# Altium_-_Maltron_S_Edition_-_Schematic.net
KiCad netlist of a schematic drawn in Altium Designer
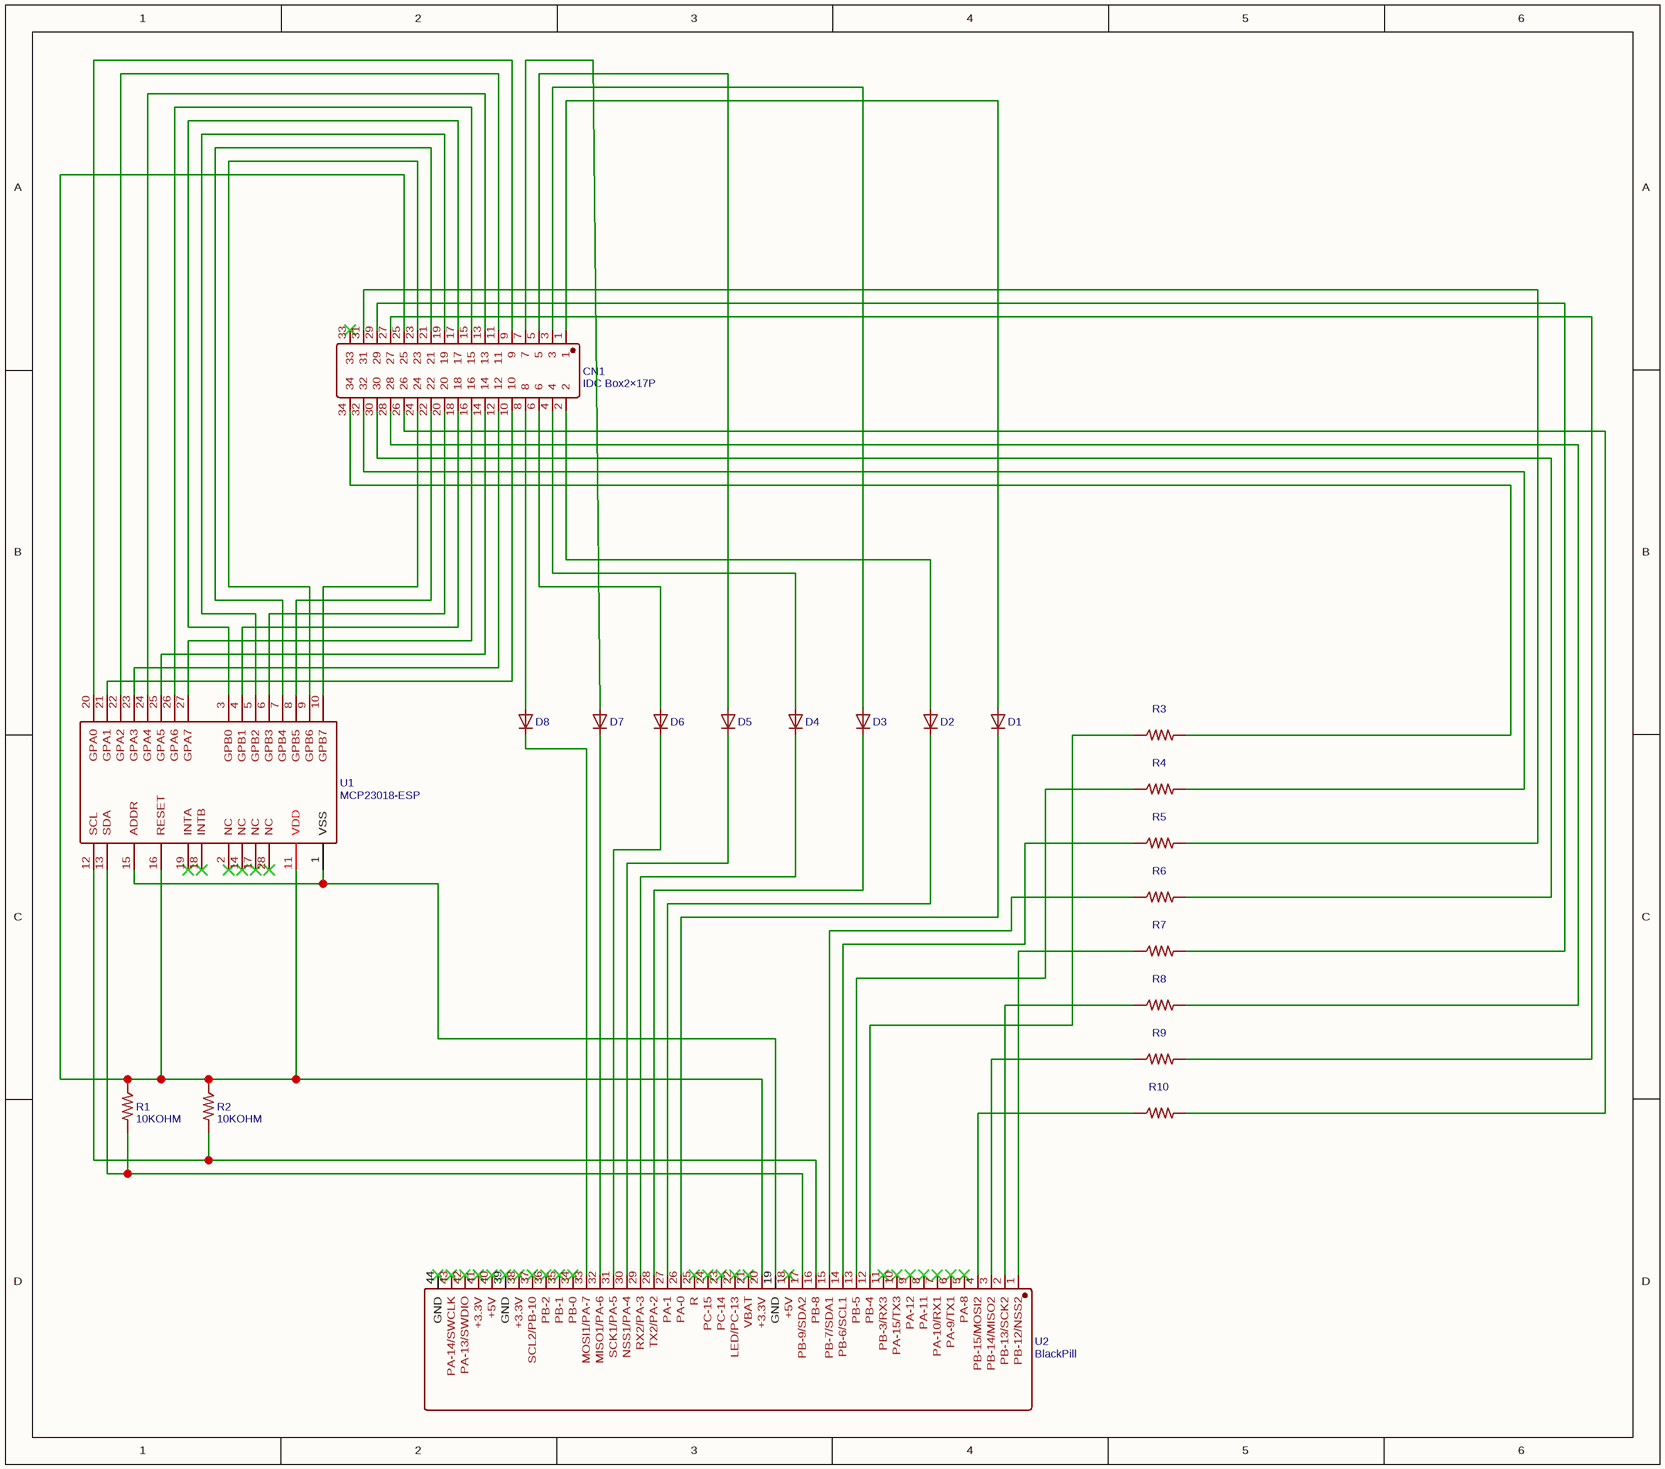
[diagram p0: Altium - Maltron_S_Edition - Schematic.schdoc]

(export (version "E")
  (design (tool "Eeschema 10.0.6"))
  (components
    (comp (ref "CN1")
      (value "IDC Box2×17P")
      (fields
        (field (name "BOM_MANUFACTURER PART") "IDC Box2×17P Right Angle")
        (field (name "BOM_SUPPLIER PART") "C20920")
      )
      (libsource (lib "altium-import") (part "root_3_IDC Box2×17P_"))
    )
    (comp (ref "D1")
      (value "DIODE")
      (fields (field (name "CONTRIBUTOR") "Adafruit"))
      (libsource (lib "altium-import") (part "root_3_DIODE_"))
    )
    (comp (ref "D2")
      (value "DIODE")
      (fields (field (name "CONTRIBUTOR") "Adafruit"))
      (libsource (lib "altium-import") (part "root_3_DIODE_"))
    )
    (comp (ref "D3")
      (value "DIODE")
      (fields (field (name "CONTRIBUTOR") "Adafruit"))
      (libsource (lib "altium-import") (part "root_3_DIODE_"))
    )
    (comp (ref "D4")
      (value "DIODE")
      (fields (field (name "CONTRIBUTOR") "Adafruit"))
      (libsource (lib "altium-import") (part "root_3_DIODE_"))
    )
    (comp (ref "D5")
      (value "DIODE")
      (fields (field (name "CONTRIBUTOR") "Adafruit"))
      (libsource (lib "altium-import") (part "root_3_DIODE_"))
    )
    (comp (ref "D6")
      (value "DIODE")
      (fields (field (name "CONTRIBUTOR") "Adafruit"))
      (libsource (lib "altium-import") (part "root_3_DIODE_"))
    )
    (comp (ref "D7")
      (value "DIODE")
      (fields (field (name "CONTRIBUTOR") "Adafruit"))
      (libsource (lib "altium-import") (part "root_3_DIODE_"))
    )
    (comp (ref "D8")
      (value "DIODE")
      (fields (field (name "CONTRIBUTOR") "Adafruit"))
      (libsource (lib "altium-import") (part "root_3_DIODE_"))
    )
    (comp (ref "R1")
      (value "10KOHM")
      (description "RES-09435")
      (fields (field (name "CONTRIBUTOR") "SparkFun"))
      (libsource (lib "altium-import") (part "root_3_10KOHM_"))
    )
    (comp (ref "R2")
      (value "10KOHM")
      (description "RES-09435")
      (fields (field (name "CONTRIBUTOR") "SparkFun"))
      (libsource (lib "altium-import") (part "root_3_10KOHM_"))
    )
    (comp (ref "R3")
      (value "10OHM-1_4W-5%(PTH)HORIZ-KIT")
      (description "RES-10698")
      (fields (field (name "CONTRIBUTOR") "SparkFun"))
      (libsource (lib "altium-import") (part "root_0_10OHM-1_4W-5%(PTH)HORIZ-KIT_"))
    )
    (comp (ref "R4")
      (value "10OHM-1_4W-5%(PTH)HORIZ-KIT")
      (description "RES-10698")
      (fields (field (name "CONTRIBUTOR") "SparkFun"))
      (libsource (lib "altium-import") (part "root_0_10OHM-1_4W-5%(PTH)HORIZ-KIT_"))
    )
    (comp (ref "R5")
      (value "10OHM-1_4W-5%(PTH)HORIZ-KIT")
      (description "RES-10698")
      (fields (field (name "CONTRIBUTOR") "SparkFun"))
      (libsource (lib "altium-import") (part "root_0_10OHM-1_4W-5%(PTH)HORIZ-KIT_"))
    )
    (comp (ref "R6")
      (value "10OHM-1_4W-5%(PTH)HORIZ-KIT")
      (description "RES-10698")
      (fields (field (name "CONTRIBUTOR") "SparkFun"))
      (libsource (lib "altium-import") (part "root_0_10OHM-1_4W-5%(PTH)HORIZ-KIT_"))
    )
    (comp (ref "R7")
      (value "10OHM-1_4W-5%(PTH)HORIZ-KIT")
      (description "RES-10698")
      (fields (field (name "CONTRIBUTOR") "SparkFun"))
      (libsource (lib "altium-import") (part "root_0_10OHM-1_4W-5%(PTH)HORIZ-KIT_"))
    )
    (comp (ref "R8")
      (value "10OHM-1_4W-5%(PTH)HORIZ-KIT")
      (description "RES-10698")
      (fields (field (name "CONTRIBUTOR") "SparkFun"))
      (libsource (lib "altium-import") (part "root_0_10OHM-1_4W-5%(PTH)HORIZ-KIT_"))
    )
    (comp (ref "R9")
      (value "10OHM-1_4W-5%(PTH)HORIZ-KIT")
      (description "RES-10698")
      (fields (field (name "CONTRIBUTOR") "SparkFun"))
      (libsource (lib "altium-import") (part "root_0_10OHM-1_4W-5%(PTH)HORIZ-KIT_"))
    )
    (comp (ref "R10")
      (value "10OHM-1_4W-5%(PTH)HORIZ-KIT")
      (description "RES-10698")
      (fields (field (name "CONTRIBUTOR") "SparkFun"))
      (libsource (lib "altium-import") (part "root_0_10OHM-1_4W-5%(PTH)HORIZ-KIT_"))
    )
    (comp (ref "U1") (value "MCP23018-ESP") (libsource (lib "altium-import") (part "root_1_MCP23018-ESP_")))
    (comp (ref "U2")
      (value "BlackPill")
      (fields (field (name "CONTRIBUTOR") "Michael Schramm"))
      (libsource (lib "altium-import") (part "root_3_BlackPill_"))
    )
  )
  (nets
    (net (code "1") (name "Net-(CN1-Pad1)") (class "Default")
      (node (ref "CN1") (pin "1") (pinfunction "1_1") (pintype "passive"))
      (node (ref "D1") (pin "A") (pinfunction "A_A") (pintype "passive"))
    )
    (net (code "2") (name "Net-(CN1-Pad2)") (class "Default")
      (node (ref "CN1") (pin "2") (pinfunction "2_2") (pintype "passive"))
      (node (ref "D2") (pin "A") (pinfunction "A_A") (pintype "passive"))
    )
    (net (code "3") (name "Net-(CN1-Pad3)") (class "Default")
      (node (ref "CN1") (pin "3") (pinfunction "3_3") (pintype "passive"))
      (node (ref "D3") (pin "A") (pinfunction "A_A") (pintype "passive"))
    )
    (net (code "4") (name "Net-(CN1-Pad4)") (class "Default")
      (node (ref "CN1") (pin "4") (pinfunction "4_4") (pintype "passive"))
      (node (ref "D4") (pin "A") (pinfunction "A_A") (pintype "passive"))
    )
    (net (code "5") (name "Net-(CN1-Pad5)") (class "Default")
      (node (ref "CN1") (pin "5") (pinfunction "5_5") (pintype "passive"))
      (node (ref "D5") (pin "A") (pinfunction "A_A") (pintype "passive"))
    )
    (net (code "6") (name "Net-(CN1-Pad6)") (class "Default")
      (node (ref "CN1") (pin "6") (pinfunction "6_6") (pintype "passive"))
      (node (ref "D6") (pin "A") (pinfunction "A_A") (pintype "passive"))
    )
    (net (code "7") (name "Net-(CN1-Pad7)") (class "Default")
      (node (ref "CN1") (pin "7") (pinfunction "7_7") (pintype "passive"))
      (node (ref "D7") (pin "A") (pinfunction "A_A") (pintype "passive"))
    )
    (net (code "8") (name "Net-(CN1-Pad8)") (class "Default")
      (node (ref "CN1") (pin "8") (pinfunction "8_8") (pintype "passive"))
      (node (ref "D8") (pin "A") (pinfunction "A_A") (pintype "passive"))
    )
    (net (code "9") (name "Net-(CN1-Pad26)") (class "Default")
      (node (ref "CN1") (pin "26") (pinfunction "26_26") (pintype "passive"))
      (node (ref "R10") (pin "2") (pinfunction "2_2") (pintype "passive"))
    )
    (net (code "10") (name "Net-(CN1-Pad27)") (class "Default")
      (node (ref "CN1") (pin "27") (pinfunction "27_27") (pintype "passive"))
      (node (ref "R9") (pin "2") (pinfunction "2_2") (pintype "passive"))
    )
    (net (code "11") (name "Net-(CN1-Pad28)") (class "Default")
      (node (ref "CN1") (pin "28") (pinfunction "28_28") (pintype "passive"))
      (node (ref "R8") (pin "2") (pinfunction "2_2") (pintype "passive"))
    )
    (net (code "12") (name "Net-(CN1-Pad29)") (class "Default")
      (node (ref "CN1") (pin "29") (pinfunction "29_29") (pintype "passive"))
      (node (ref "R7") (pin "2") (pinfunction "2_2") (pintype "passive"))
    )
    (net (code "13") (name "Net-(CN1-Pad30)") (class "Default")
      (node (ref "CN1") (pin "30") (pinfunction "30_30") (pintype "passive"))
      (node (ref "R6") (pin "2") (pinfunction "2_2") (pintype "passive"))
    )
    (net (code "14") (name "Net-(CN1-Pad31)") (class "Default")
      (node (ref "CN1") (pin "31") (pinfunction "31_31") (pintype "passive"))
      (node (ref "R5") (pin "2") (pinfunction "2_2") (pintype "passive"))
    )
    (net (code "15") (name "Net-(CN1-Pad32)") (class "Default")
      (node (ref "CN1") (pin "32") (pinfunction "32_32") (pintype "passive"))
      (node (ref "R4") (pin "2") (pinfunction "2_2") (pintype "passive"))
    )
    (net (code "16") (name "Net-(CN1-Pad34)") (class "Default")
      (node (ref "CN1") (pin "34") (pinfunction "34_34") (pintype "passive"))
      (node (ref "R3") (pin "2") (pinfunction "2_2") (pintype "passive"))
    )
    (net (code "17") (name "Net-(U1-ADDR)") (class "Default")
      (node (ref "U1") (pin "1") (pinfunction "VSS_1") (pintype "passive"))
      (node (ref "U1") (pin "15") (pinfunction "ADDR_15") (pintype "passive"))
      (node (ref "U2") (pin "19") (pinfunction "GND_19") (pintype "passive"))
    )
    (net (code "18") (name "Net-(U1-GPA0)") (class "Default")
      (node (ref "CN1") (pin "9") (pinfunction "9_9") (pintype "passive"))
      (node (ref "U1") (pin "20") (pinfunction "GPA0_20") (pintype "passive"))
    )
    (net (code "19") (name "Net-(U1-GPA1)") (class "Default")
      (node (ref "CN1") (pin "10") (pinfunction "10_10") (pintype "passive"))
      (node (ref "U1") (pin "21") (pinfunction "GPA1_21") (pintype "passive"))
    )
    (net (code "20") (name "Net-(U1-GPA2)") (class "Default")
      (node (ref "CN1") (pin "11") (pinfunction "11_11") (pintype "passive"))
      (node (ref "U1") (pin "22") (pinfunction "GPA2_22") (pintype "passive"))
    )
    (net (code "21") (name "Net-(U1-GPA3)") (class "Default")
      (node (ref "CN1") (pin "12") (pinfunction "12_12") (pintype "passive"))
      (node (ref "U1") (pin "23") (pinfunction "GPA3_23") (pintype "passive"))
    )
    (net (code "22") (name "Net-(U1-GPA4)") (class "Default")
      (node (ref "CN1") (pin "13") (pinfunction "13_13") (pintype "passive"))
      (node (ref "U1") (pin "24") (pinfunction "GPA4_24") (pintype "passive"))
    )
    (net (code "23") (name "Net-(U1-GPA5)") (class "Default")
      (node (ref "CN1") (pin "14") (pinfunction "14_14") (pintype "passive"))
      (node (ref "U1") (pin "25") (pinfunction "GPA5_25") (pintype "passive"))
    )
    (net (code "24") (name "Net-(U1-GPA6)") (class "Default")
      (node (ref "CN1") (pin "15") (pinfunction "15_15") (pintype "passive"))
      (node (ref "U1") (pin "26") (pinfunction "GPA6_26") (pintype "passive"))
    )
    (net (code "25") (name "Net-(U1-GPA7)") (class "Default")
      (node (ref "CN1") (pin "16") (pinfunction "16_16") (pintype "passive"))
      (node (ref "U1") (pin "27") (pinfunction "GPA7_27") (pintype "passive"))
    )
    (net (code "26") (name "Net-(U1-GPB0)") (class "Default")
      (node (ref "CN1") (pin "17") (pinfunction "17_17") (pintype "passive"))
      (node (ref "U1") (pin "3") (pinfunction "GPB0_3") (pintype "passive"))
    )
    (net (code "27") (name "Net-(U1-GPB1)") (class "Default")
      (node (ref "CN1") (pin "18") (pinfunction "18_18") (pintype "passive"))
      (node (ref "U1") (pin "4") (pinfunction "GPB1_4") (pintype "passive"))
    )
    (net (code "28") (name "Net-(U1-GPB2)") (class "Default")
      (node (ref "CN1") (pin "19") (pinfunction "19_19") (pintype "passive"))
      (node (ref "U1") (pin "5") (pinfunction "GPB2_5") (pintype "passive"))
    )
    (net (code "29") (name "Net-(U1-GPB3)") (class "Default")
      (node (ref "CN1") (pin "20") (pinfunction "20_20") (pintype "passive"))
      (node (ref "U1") (pin "6") (pinfunction "GPB3_6") (pintype "passive"))
    )
    (net (code "30") (name "Net-(U1-GPB4)") (class "Default")
      (node (ref "CN1") (pin "21") (pinfunction "21_21") (pintype "passive"))
      (node (ref "U1") (pin "7") (pinfunction "GPB4_7") (pintype "passive"))
    )
    (net (code "31") (name "Net-(U1-GPB5)") (class "Default")
      (node (ref "CN1") (pin "22") (pinfunction "22_22") (pintype "passive"))
      (node (ref "U1") (pin "8") (pinfunction "GPB5_8") (pintype "passive"))
    )
    (net (code "32") (name "Net-(U1-GPB6)") (class "Default")
      (node (ref "CN1") (pin "23") (pinfunction "23_23") (pintype "passive"))
      (node (ref "U1") (pin "9") (pinfunction "GPB6_9") (pintype "passive"))
    )
    (net (code "33") (name "Net-(U1-GPB7)") (class "Default")
      (node (ref "CN1") (pin "24") (pinfunction "24_24") (pintype "passive"))
      (node (ref "U1") (pin "10") (pinfunction "GPB7_10") (pintype "passive"))
    )
    (net (code "34") (name "Net-(U1-RESET)") (class "Default")
      (node (ref "CN1") (pin "25") (pinfunction "25_25") (pintype "passive"))
      (node (ref "R1") (pin "1") (pinfunction "1_1") (pintype "passive"))
      (node (ref "R2") (pin "1") (pinfunction "1_1") (pintype "passive"))
      (node (ref "U1") (pin "11") (pinfunction "VDD_11") (pintype "passive"))
      (node (ref "U1") (pin "16") (pinfunction "RESET_16") (pintype "passive"))
      (node (ref "U2") (pin "20") (pinfunction "+3.3V_20") (pintype "passive"))
    )
    (net (code "35") (name "Net-(U1-SCL)") (class "Default")
      (node (ref "R2") (pin "2") (pinfunction "2_2") (pintype "passive"))
      (node (ref "U1") (pin "12") (pinfunction "SCL_12") (pintype "passive"))
      (node (ref "U2") (pin "16") (pinfunction "PB-8_16") (pintype "passive"))
    )
    (net (code "36") (name "Net-(U1-SDA)") (class "Default")
      (node (ref "R1") (pin "2") (pinfunction "2_2") (pintype "passive"))
      (node (ref "U1") (pin "13") (pinfunction "SDA_13") (pintype "passive"))
      (node (ref "U2") (pin "17") (pinfunction "PB-9/SDA2_17") (pintype "passive"))
    )
    (net (code "37") (name "Net-(U2-MISO1{slash}PA-6)") (class "Default")
      (node (ref "D7") (pin "C") (pinfunction "C_C") (pintype "passive"))
      (node (ref "U2") (pin "32") (pinfunction "MISO1/PA-6_32") (pintype "passive"))
    )
    (net (code "38") (name "Net-(U2-MOSI1{slash}PA-7)") (class "Default")
      (node (ref "D8") (pin "C") (pinfunction "C_C") (pintype "passive"))
      (node (ref "U2") (pin "33") (pinfunction "MOSI1/PA-7_33") (pintype "passive"))
    )
    (net (code "39") (name "Net-(U2-NSS1{slash}PA-4)") (class "Default")
      (node (ref "D5") (pin "C") (pinfunction "C_C") (pintype "passive"))
      (node (ref "U2") (pin "30") (pinfunction "NSS1/PA-4_30") (pintype "passive"))
    )
    (net (code "40") (name "Net-(U2-PA-0)") (class "Default")
      (node (ref "D1") (pin "C") (pinfunction "C_C") (pintype "passive"))
      (node (ref "U2") (pin "26") (pinfunction "PA-0_26") (pintype "passive"))
    )
    (net (code "41") (name "Net-(U2-PA-1)") (class "Default")
      (node (ref "D2") (pin "C") (pinfunction "C_C") (pintype "passive"))
      (node (ref "U2") (pin "27") (pinfunction "PA-1_27") (pintype "passive"))
    )
    (net (code "42") (name "Net-(U2-PB-4)") (class "Default")
      (node (ref "R3") (pin "1") (pinfunction "1_1") (pintype "passive"))
      (node (ref "U2") (pin "12") (pinfunction "PB-4_12") (pintype "passive"))
    )
    (net (code "43") (name "Net-(U2-PB-5)") (class "Default")
      (node (ref "R4") (pin "1") (pinfunction "1_1") (pintype "passive"))
      (node (ref "U2") (pin "13") (pinfunction "PB-5_13") (pintype "passive"))
    )
    (net (code "44") (name "Net-(U2-PB-6{slash}SCL1)") (class "Default")
      (node (ref "R5") (pin "1") (pinfunction "1_1") (pintype "passive"))
      (node (ref "U2") (pin "14") (pinfunction "PB-6/SCL1_14") (pintype "passive"))
    )
    (net (code "45") (name "Net-(U2-PB-7{slash}SDA1)") (class "Default")
      (node (ref "R6") (pin "1") (pinfunction "1_1") (pintype "passive"))
      (node (ref "U2") (pin "15") (pinfunction "PB-7/SDA1_15") (pintype "passive"))
    )
    (net (code "46") (name "Net-(U2-PB-12{slash}NSS2)") (class "Default")
      (node (ref "R7") (pin "1") (pinfunction "1_1") (pintype "passive"))
      (node (ref "U2") (pin "1") (pinfunction "PB-12/NSS2_1") (pintype "passive"))
    )
    (net (code "47") (name "Net-(U2-PB-13{slash}SCK2)") (class "Default")
      (node (ref "R8") (pin "1") (pinfunction "1_1") (pintype "passive"))
      (node (ref "U2") (pin "2") (pinfunction "PB-13/SCK2_2") (pintype "passive"))
    )
    (net (code "48") (name "Net-(U2-PB-14{slash}MISO2)") (class "Default")
      (node (ref "R9") (pin "1") (pinfunction "1_1") (pintype "passive"))
      (node (ref "U2") (pin "3") (pinfunction "PB-14/MISO2_3") (pintype "passive"))
    )
    (net (code "49") (name "Net-(U2-PB-15{slash}MOSI2)") (class "Default")
      (node (ref "R10") (pin "1") (pinfunction "1_1") (pintype "passive"))
      (node (ref "U2") (pin "4") (pinfunction "PB-15/MOSI2_4") (pintype "passive"))
    )
    (net (code "50") (name "Net-(U2-RX2{slash}PA-3)") (class "Default")
      (node (ref "D4") (pin "C") (pinfunction "C_C") (pintype "passive"))
      (node (ref "U2") (pin "29") (pinfunction "RX2/PA-3_29") (pintype "passive"))
    )
    (net (code "51") (name "Net-(U2-SCK1{slash}PA-5)") (class "Default")
      (node (ref "D6") (pin "C") (pinfunction "C_C") (pintype "passive"))
      (node (ref "U2") (pin "31") (pinfunction "SCK1/PA-5_31") (pintype "passive"))
    )
    (net (code "52") (name "Net-(U2-TX2{slash}PA-2)") (class "Default")
      (node (ref "D3") (pin "C") (pinfunction "C_C") (pintype "passive"))
      (node (ref "U2") (pin "28") (pinfunction "TX2/PA-2_28") (pintype "passive"))
    )
    (net (code "53") (name "unconnected-(CN1-Pad33)") (class "Default")
      (node (ref "CN1") (pin "33") (pinfunction "33_33") (pintype "passive+no_connect"))
    )
    (net (code "54") (name "unconnected-(U1-INTA-Pad19)") (class "Default")
      (node (ref "U1") (pin "19") (pinfunction "INTA_19") (pintype "passive+no_connect"))
    )
    (net (code "55") (name "unconnected-(U1-INTB-Pad18)") (class "Default")
      (node (ref "U1") (pin "18") (pinfunction "INTB_18") (pintype "passive+no_connect"))
    )
    (net (code "56") (name "unconnected-(U1-NC-Pad2)") (class "Default")
      (node (ref "U1") (pin "2") (pinfunction "NC_2") (pintype "passive+no_connect"))
    )
    (net (code "57") (name "unconnected-(U1-NC-Pad14)") (class "Default")
      (node (ref "U1") (pin "14") (pinfunction "NC_14") (pintype "passive+no_connect"))
    )
    (net (code "58") (name "unconnected-(U1-NC-Pad17)") (class "Default")
      (node (ref "U1") (pin "17") (pinfunction "NC_17") (pintype "passive+no_connect"))
    )
    (net (code "59") (name "unconnected-(U1-NC-Pad28)") (class "Default")
      (node (ref "U1") (pin "28") (pinfunction "NC_28") (pintype "passive+no_connect"))
    )
    (net (code "60") (name "unconnected-(U2-+3.3V-Pad38)") (class "Default")
      (node (ref "U2") (pin "38") (pinfunction "+3.3V_38") (pintype "passive+no_connect"))
    )
    (net (code "61") (name "unconnected-(U2-+3.3V-Pad41)") (class "Default")
      (node (ref "U2") (pin "41") (pinfunction "+3.3V_41") (pintype "passive+no_connect"))
    )
    (net (code "62") (name "unconnected-(U2-+5V-Pad18)") (class "Default")
      (node (ref "U2") (pin "18") (pinfunction "+5V_18") (pintype "passive+no_connect"))
    )
    (net (code "63") (name "unconnected-(U2-+5V-Pad40)") (class "Default")
      (node (ref "U2") (pin "40") (pinfunction "+5V_40") (pintype "passive+no_connect"))
    )
    (net (code "64") (name "unconnected-(U2-GND-Pad39)") (class "Default")
      (node (ref "U2") (pin "39") (pinfunction "GND_39") (pintype "passive+no_connect"))
    )
    (net (code "65") (name "unconnected-(U2-GND-Pad44)") (class "Default")
      (node (ref "U2") (pin "44") (pinfunction "GND_44") (pintype "passive+no_connect"))
    )
    (net (code "66") (name "unconnected-(U2-LED{slash}PC-13-Pad22)") (class "Default")
      (node (ref "U2") (pin "22") (pinfunction "LED/PC-13_22") (pintype "passive+no_connect"))
    )
    (net (code "67") (name "unconnected-(U2-PA-8-Pad5)") (class "Default")
      (node (ref "U2") (pin "5") (pinfunction "PA-8_5") (pintype "passive+no_connect"))
    )
    (net (code "68") (name "unconnected-(U2-PA-9{slash}TX1-Pad6)") (class "Default")
      (node (ref "U2") (pin "6") (pinfunction "PA-9/TX1_6") (pintype "passive+no_connect"))
    )
    (net (code "69") (name "unconnected-(U2-PA-10{slash}RX1-Pad7)") (class "Default")
      (node (ref "U2") (pin "7") (pinfunction "PA-10/RX1_7") (pintype "passive+no_connect"))
    )
    (net (code "70") (name "unconnected-(U2-PA-11-Pad8)") (class "Default")
      (node (ref "U2") (pin "8") (pinfunction "PA-11_8") (pintype "passive+no_connect"))
    )
    (net (code "71") (name "unconnected-(U2-PA-12-Pad9)") (class "Default")
      (node (ref "U2") (pin "9") (pinfunction "PA-12_9") (pintype "passive+no_connect"))
    )
    (net (code "72") (name "unconnected-(U2-PA-13{slash}SWDIO-Pad42)") (class "Default")
      (node (ref "U2") (pin "42") (pinfunction "PA-13/SWDIO_42") (pintype "passive+no_connect"))
    )
    (net (code "73") (name "unconnected-(U2-PA-14{slash}SWCLK-Pad43)") (class "Default")
      (node (ref "U2") (pin "43") (pinfunction "PA-14/SWCLK_43") (pintype "passive+no_connect"))
    )
    (net (code "74") (name "unconnected-(U2-PA-15{slash}TX3-Pad10)") (class "Default")
      (node (ref "U2") (pin "10") (pinfunction "PA-15/TX3_10") (pintype "passive+no_connect"))
    )
    (net (code "75") (name "unconnected-(U2-PB-0-Pad34)") (class "Default")
      (node (ref "U2") (pin "34") (pinfunction "PB-0_34") (pintype "passive+no_connect"))
    )
    (net (code "76") (name "unconnected-(U2-PB-1-Pad35)") (class "Default")
      (node (ref "U2") (pin "35") (pinfunction "PB-1_35") (pintype "passive+no_connect"))
    )
    (net (code "77") (name "unconnected-(U2-PB-2-Pad36)") (class "Default")
      (node (ref "U2") (pin "36") (pinfunction "PB-2_36") (pintype "passive+no_connect"))
    )
    (net (code "78") (name "unconnected-(U2-PB-3{slash}RX3-Pad11)") (class "Default")
      (node (ref "U2") (pin "11") (pinfunction "PB-3/RX3_11") (pintype "passive+no_connect"))
    )
    (net (code "79") (name "unconnected-(U2-PC-14-Pad23)") (class "Default")
      (node (ref "U2") (pin "23") (pinfunction "PC-14_23") (pintype "passive+no_connect"))
    )
    (net (code "80") (name "unconnected-(U2-PC-15-Pad24)") (class "Default")
      (node (ref "U2") (pin "24") (pinfunction "PC-15_24") (pintype "passive+no_connect"))
    )
    (net (code "81") (name "unconnected-(U2-R-Pad25)") (class "Default")
      (node (ref "U2") (pin "25") (pinfunction "R_25") (pintype "passive+no_connect"))
    )
    (net (code "82") (name "unconnected-(U2-SCL2{slash}PB-10-Pad37)") (class "Default")
      (node (ref "U2") (pin "37") (pinfunction "SCL2/PB-10_37") (pintype "passive+no_connect"))
    )
    (net (code "83") (name "unconnected-(U2-VBAT-Pad21)") (class "Default")
      (node (ref "U2") (pin "21") (pinfunction "VBAT_21") (pintype "passive+no_connect"))
    )
  )
)
